# Nucleo_Connector.net
KiCad netlist of a schematic drawn in Altium Designer
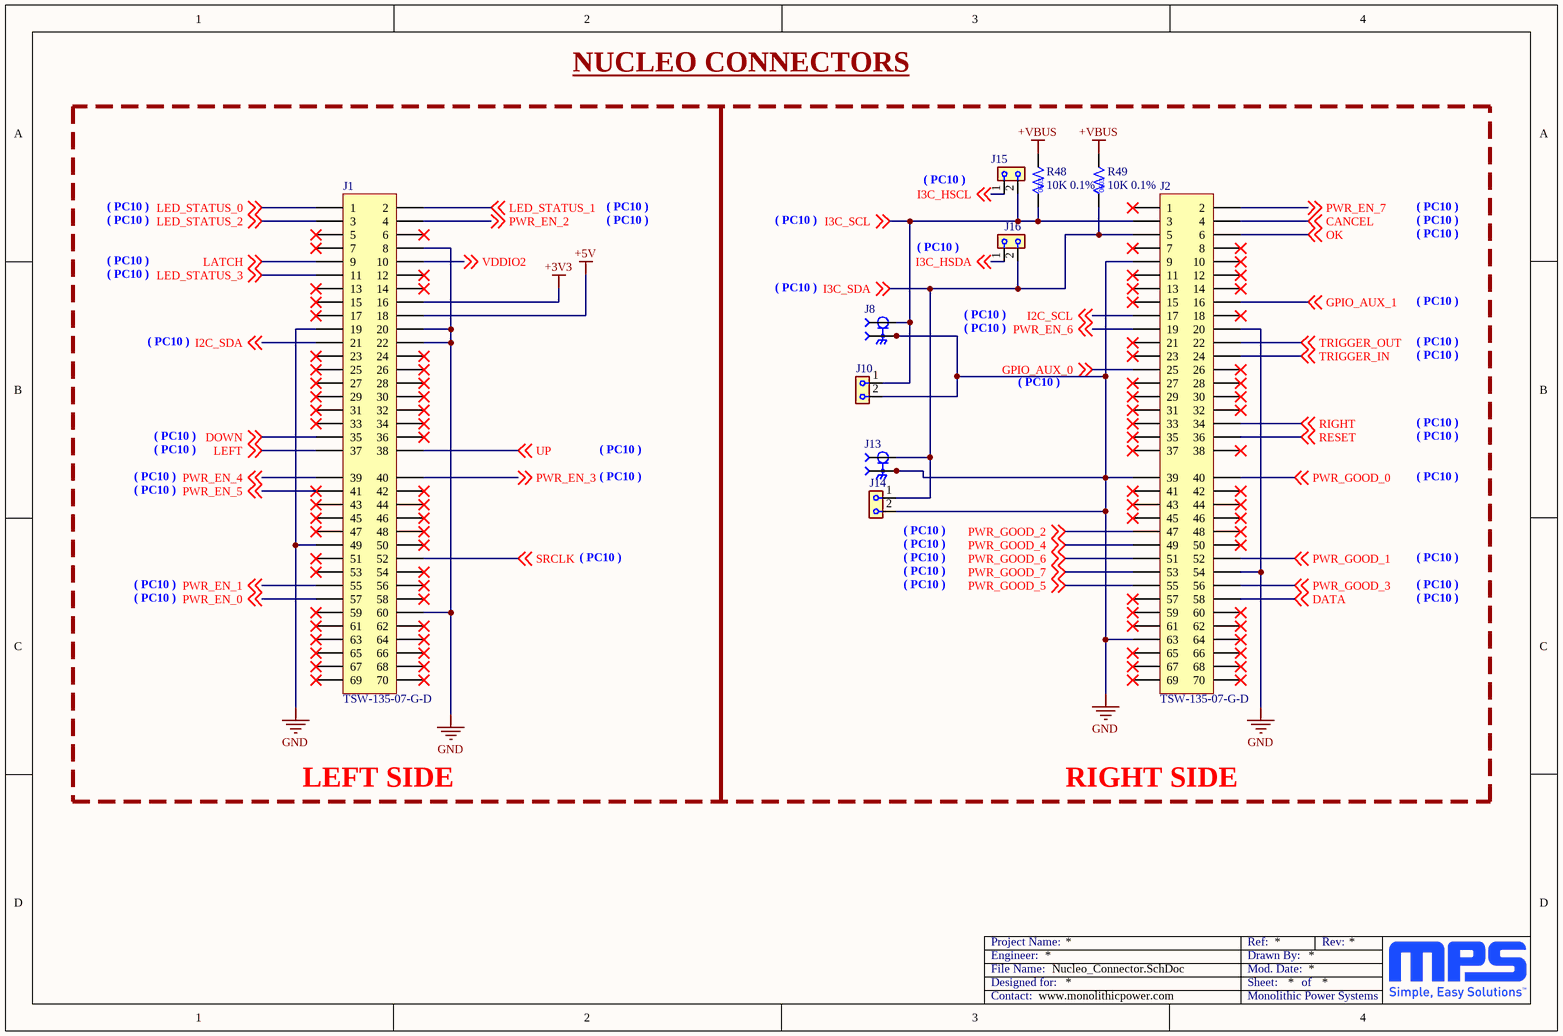
[diagram p0: Nucleo_Connector.SchDoc]

(export (version "E")
  (design (tool "Eeschema 10.0.6"))
  (components
    (comp (ref "J1")
      (value "TSW-135-07-G-D")
      (footprint "CON_SAMTEC_TSW-135-07-X-D")
      (description "Header, 35x2, 2,54mm, VR, TH, Height 5.84mm/2.54mm")
      (fields (field (name "MANUFACTURER") "Samtec"))
      (libsource (lib "DDR5_Nucleo_Shield_Symbols") (part "TSW-135-07-G-D"))
    )
    (comp (ref "J2")
      (value "TSW-135-07-G-D")
      (footprint "CON_SAMTEC_TSW-135-07-X-D")
      (description "Header, 35x2, 2,54mm, VR, TH, Height 5.84mm/2.54mm")
      (fields (field (name "MANUFACTURER") "Samtec"))
      (libsource (lib "DDR5_Nucleo_Shield_Symbols") (part "TSW-135-07-G-D"))
    )
    (comp (ref "J8")
      (value "MMCX-J-P-H-ST-TH1")
      (footprint "SAMTEC_MMCX-J-P-H-ST-TH1")
      (description "RF Connectors / Coaxial Connectors 50 OHM MMCX JACK OR PLUG")
      (fields (field (name "MANUFACTURER") "Samtec Inc."))
      (libsource (lib "DDR5_Nucleo_Shield_Symbols") (part "MMCX-J-P-H-ST-TH1"))
    )
    (comp (ref "J10")
      (value "TSW-102-07-F-S")
      (footprint "HEADER/VERT/1X2/M/P2.54")
      (description "Alojamientos de cables y cabecera 2.54MM CLASSIC PCB HDR STRIP")
      (fields (field (name "MANUFACTURER") "SAMTEC"))
      (libsource (lib "") (part "TSW-102-07-F-S_1"))
    )
    (comp (ref "J13")
      (value "MMCX-J-P-H-ST-TH1")
      (footprint "SAMTEC_MMCX-J-P-H-ST-TH1")
      (description "RF Connectors / Coaxial Connectors 50 OHM MMCX JACK OR PLUG")
      (fields (field (name "MANUFACTURER") "Samtec Inc."))
      (libsource (lib "DDR5_Nucleo_Shield_Symbols") (part "MMCX-J-P-H-ST-TH1"))
    )
    (comp (ref "J14")
      (value "TSW-102-07-F-S")
      (footprint "HEADER/VERT/1X2/M/P2.54")
      (description "Alojamientos de cables y cabecera 2.54MM CLASSIC PCB HDR STRIP")
      (fields (field (name "MANUFACTURER") "SAMTEC"))
      (libsource (lib "") (part "TSW-102-07-F-S_1"))
    )
    (comp (ref "J15")
      (value "TSW-102-07-F-S")
      (footprint "HEADER/VERT/1X2/M/P2.54")
      (description "Alojamientos de cables y cabecera 2.54MM CLASSIC PCB HDR STRIP")
      (fields (field (name "MANUFACTURER") "SAMTEC"))
      (libsource (lib "DDR5_Nucleo_Shield_Symbols") (part "TSW-102-07-F-S"))
    )
    (comp (ref "J16")
      (value "TSW-102-07-F-S")
      (footprint "HEADER/VERT/1X2/M/P2.54")
      (description "Alojamientos de cables y cabecera 2.54MM CLASSIC PCB HDR STRIP")
      (fields (field (name "MANUFACTURER") "SAMTEC"))
      (libsource (lib "DDR5_Nucleo_Shield_Symbols") (part "TSW-102-07-F-S"))
    )
    (comp (ref "R48")
      (value "10K 0.1%")
      (footprint "CC/NM 0603")
      (description "Thin Film Resistors - SMD 1/10watts 10K .1%")
      (fields
        (field (name "MANUFACTURER") "Bourns")
        (field (name "MANUFACTURER PART NUMBER") "CRT0603-BY-1002ELF")
      )
      (libsource (lib "DDR5_Nucleo_Shield_Symbols") (part "CRT0603-BY-1002ELF"))
    )
    (comp (ref "R49")
      (value "10K 0.1%")
      (footprint "CC/NM 0603")
      (description "Thin Film Resistors - SMD 1/10watts 10K .1%")
      (fields
        (field (name "MANUFACTURER") "Bourns")
        (field (name "MANUFACTURER PART NUMBER") "CRT0603-BY-1002ELF")
      )
      (libsource (lib "DDR5_Nucleo_Shield_Symbols") (part "CRT0603-BY-1002ELF"))
    )
  )
  (nets
    (net (code "1") (name "+3V3") (class "Default")
      (node (ref "J1") (pin "16") (pinfunction "16_16") (pintype "passive"))
    )
    (net (code "2") (name "+5V") (class "Default")
      (node (ref "J1") (pin "18") (pinfunction "18_18") (pintype "passive"))
    )
    (net (code "3") (name "+VBUS") (class "Default")
      (node (ref "R48") (pin "2") (pinfunction "2_2") (pintype "passive"))
      (node (ref "R49") (pin "2") (pinfunction "2_2") (pintype "passive"))
    )
    (net (code "4") (name "CANCEL") (class "Default")
      (node (ref "J2") (pin "4") (pinfunction "4_4") (pintype "passive"))
    )
    (net (code "5") (name "DATA") (class "Default")
      (node (ref "J2") (pin "58") (pinfunction "58_58") (pintype "passive"))
    )
    (net (code "6") (name "DOWN") (class "Default")
      (node (ref "J1") (pin "35") (pinfunction "35_35") (pintype "passive"))
    )
    (net (code "7") (name "GND") (class "Default")
      (node (ref "J1") (pin "19") (pinfunction "19_19") (pintype "passive"))
      (node (ref "J1") (pin "20") (pinfunction "20_20") (pintype "passive"))
      (node (ref "J1") (pin "22") (pinfunction "22_22") (pintype "passive"))
      (node (ref "J1") (pin "49") (pinfunction "49_49") (pintype "passive"))
      (node (ref "J1") (pin "60") (pinfunction "60_60") (pintype "passive"))
      (node (ref "J1") (pin "8") (pinfunction "8_8") (pintype "passive"))
      (node (ref "J10") (pin "2") (pinfunction "2_2") (pintype "passive"))
      (node (ref "J13") (pin "S1") (pinfunction "2_S1") (pintype "passive"))
      (node (ref "J13") (pin "S2") (pinfunction "2_S2") (pintype "passive"))
      (node (ref "J13") (pin "S3") (pinfunction "2_S3") (pintype "passive"))
      (node (ref "J13") (pin "S4") (pinfunction "2_S4") (pintype "passive"))
      (node (ref "J14") (pin "2") (pinfunction "2_2") (pintype "passive"))
      (node (ref "J2") (pin "20") (pinfunction "20_20") (pintype "passive"))
      (node (ref "J2") (pin "39") (pinfunction "39_39") (pintype "passive"))
      (node (ref "J2") (pin "54") (pinfunction "54_54") (pintype "passive"))
      (node (ref "J2") (pin "63") (pinfunction "63_63") (pintype "passive"))
      (node (ref "J2") (pin "9") (pinfunction "9_9") (pintype "passive"))
      (node (ref "J8") (pin "S1") (pinfunction "2_S1") (pintype "passive"))
      (node (ref "J8") (pin "S2") (pinfunction "2_S2") (pintype "passive"))
      (node (ref "J8") (pin "S3") (pinfunction "2_S3") (pintype "passive"))
      (node (ref "J8") (pin "S4") (pinfunction "2_S4") (pintype "passive"))
    )
    (net (code "8") (name "GPIO_AUX_0") (class "Default")
      (node (ref "J2") (pin "25") (pinfunction "25_25") (pintype "passive"))
    )
    (net (code "9") (name "GPIO_AUX_1") (class "Default")
      (node (ref "J2") (pin "16") (pinfunction "16_16") (pintype "passive"))
    )
    (net (code "10") (name "I2C_SCL") (class "Default")
      (node (ref "J2") (pin "17") (pinfunction "17_17") (pintype "passive"))
    )
    (net (code "11") (name "I2C_SDA") (class "Default")
      (node (ref "J1") (pin "21") (pinfunction "21_21") (pintype "passive"))
    )
    (net (code "12") (name "I3C_HSCL") (class "Default")
      (node (ref "J15") (pin "1") (pinfunction "1_1") (pintype "passive"))
    )
    (net (code "13") (name "I3C_HSDA") (class "Default")
      (node (ref "J16") (pin "1") (pinfunction "1_1") (pintype "passive"))
    )
    (net (code "14") (name "I3C_SCL") (class "Default")
      (node (ref "J10") (pin "1") (pinfunction "1_1") (pintype "passive"))
      (node (ref "J15") (pin "2") (pinfunction "2_2") (pintype "passive"))
      (node (ref "J2") (pin "3") (pinfunction "3_3") (pintype "passive"))
      (node (ref "J8") (pin "1") (pinfunction "1_1") (pintype "passive"))
      (node (ref "R48") (pin "1") (pinfunction "1_1") (pintype "passive"))
    )
    (net (code "15") (name "I3C_SDA") (class "Default")
      (node (ref "J13") (pin "1") (pinfunction "1_1") (pintype "passive"))
      (node (ref "J14") (pin "1") (pinfunction "1_1") (pintype "passive"))
      (node (ref "J16") (pin "2") (pinfunction "2_2") (pintype "passive"))
      (node (ref "J2") (pin "5") (pinfunction "5_5") (pintype "passive"))
      (node (ref "R49") (pin "1") (pinfunction "1_1") (pintype "passive"))
    )
    (net (code "16") (name "LATCH") (class "Default")
      (node (ref "J1") (pin "9") (pinfunction "9_9") (pintype "passive"))
    )
    (net (code "17") (name "LED_STATUS_0") (class "Default")
      (node (ref "J1") (pin "1") (pinfunction "1_1") (pintype "passive"))
    )
    (net (code "18") (name "LED_STATUS_1") (class "Default")
      (node (ref "J1") (pin "2") (pinfunction "2_2") (pintype "passive"))
    )
    (net (code "19") (name "LED_STATUS_2") (class "Default")
      (node (ref "J1") (pin "3") (pinfunction "3_3") (pintype "passive"))
    )
    (net (code "20") (name "LED_STATUS_3") (class "Default")
      (node (ref "J1") (pin "11") (pinfunction "11_11") (pintype "passive"))
    )
    (net (code "21") (name "LEFT") (class "Default")
      (node (ref "J1") (pin "37") (pinfunction "37_37") (pintype "passive"))
    )
    (net (code "22") (name "OK") (class "Default")
      (node (ref "J2") (pin "6") (pinfunction "6_6") (pintype "passive"))
    )
    (net (code "23") (name "PWR_EN_0") (class "Default")
      (node (ref "J1") (pin "57") (pinfunction "57_57") (pintype "passive"))
    )
    (net (code "24") (name "PWR_EN_1") (class "Default")
      (node (ref "J1") (pin "55") (pinfunction "55_55") (pintype "passive"))
    )
    (net (code "25") (name "PWR_EN_2") (class "Default")
      (node (ref "J1") (pin "4") (pinfunction "4_4") (pintype "passive"))
    )
    (net (code "26") (name "PWR_EN_3") (class "Default")
      (node (ref "J1") (pin "40") (pinfunction "40_40") (pintype "passive"))
    )
    (net (code "27") (name "PWR_EN_4") (class "Default")
      (node (ref "J1") (pin "39") (pinfunction "39_39") (pintype "passive"))
    )
    (net (code "28") (name "PWR_EN_5") (class "Default")
      (node (ref "J1") (pin "41") (pinfunction "41_41") (pintype "passive"))
    )
    (net (code "29") (name "PWR_EN_6") (class "Default")
      (node (ref "J2") (pin "19") (pinfunction "19_19") (pintype "passive"))
    )
    (net (code "30") (name "PWR_EN_7") (class "Default")
      (node (ref "J2") (pin "2") (pinfunction "2_2") (pintype "passive"))
    )
    (net (code "31") (name "PWR_GOOD_0") (class "Default")
      (node (ref "J2") (pin "40") (pinfunction "40_40") (pintype "passive"))
    )
    (net (code "32") (name "PWR_GOOD_1") (class "Default")
      (node (ref "J2") (pin "52") (pinfunction "52_52") (pintype "passive"))
    )
    (net (code "33") (name "PWR_GOOD_2") (class "Default")
      (node (ref "J2") (pin "47") (pinfunction "47_47") (pintype "passive"))
    )
    (net (code "34") (name "PWR_GOOD_3") (class "Default")
      (node (ref "J2") (pin "56") (pinfunction "56_56") (pintype "passive"))
    )
    (net (code "35") (name "PWR_GOOD_4") (class "Default")
      (node (ref "J2") (pin "49") (pinfunction "49_49") (pintype "passive"))
    )
    (net (code "36") (name "PWR_GOOD_5") (class "Default")
      (node (ref "J2") (pin "55") (pinfunction "55_55") (pintype "passive"))
    )
    (net (code "37") (name "PWR_GOOD_6") (class "Default")
      (node (ref "J2") (pin "51") (pinfunction "51_51") (pintype "passive"))
    )
    (net (code "38") (name "PWR_GOOD_7") (class "Default")
      (node (ref "J2") (pin "53") (pinfunction "53_53") (pintype "passive"))
    )
    (net (code "39") (name "RESET") (class "Default")
      (node (ref "J2") (pin "36") (pinfunction "36_36") (pintype "passive"))
    )
    (net (code "40") (name "RIGHT") (class "Default")
      (node (ref "J2") (pin "34") (pinfunction "34_34") (pintype "passive"))
    )
    (net (code "41") (name "SRCLK") (class "Default")
      (node (ref "J1") (pin "52") (pinfunction "52_52") (pintype "passive"))
    )
    (net (code "42") (name "TRIGGER_IN") (class "Default")
      (node (ref "J2") (pin "24") (pinfunction "24_24") (pintype "passive"))
    )
    (net (code "43") (name "TRIGGER_OUT") (class "Default")
      (node (ref "J2") (pin "22") (pinfunction "22_22") (pintype "passive"))
    )
    (net (code "44") (name "UP") (class "Default")
      (node (ref "J1") (pin "38") (pinfunction "38_38") (pintype "passive"))
    )
    (net (code "45") (name "VDDIO2") (class "Default")
      (node (ref "J1") (pin "10") (pinfunction "10_10") (pintype "passive"))
    )
    (net (code "46") (name "unconnected-(J1-Pad5)") (class "Default")
      (node (ref "J1") (pin "5") (pinfunction "5_5") (pintype "passive+no_connect"))
    )
    (net (code "47") (name "unconnected-(J1-Pad6)") (class "Default")
      (node (ref "J1") (pin "6") (pinfunction "6_6") (pintype "passive+no_connect"))
    )
    (net (code "48") (name "unconnected-(J1-Pad7)") (class "Default")
      (node (ref "J1") (pin "7") (pinfunction "7_7") (pintype "passive+no_connect"))
    )
    (net (code "49") (name "unconnected-(J1-Pad12)") (class "Default")
      (node (ref "J1") (pin "12") (pinfunction "12_12") (pintype "passive+no_connect"))
    )
    (net (code "50") (name "unconnected-(J1-Pad13)") (class "Default")
      (node (ref "J1") (pin "13") (pinfunction "13_13") (pintype "passive+no_connect"))
    )
    (net (code "51") (name "unconnected-(J1-Pad14)") (class "Default")
      (node (ref "J1") (pin "14") (pinfunction "14_14") (pintype "passive+no_connect"))
    )
    (net (code "52") (name "unconnected-(J1-Pad15)") (class "Default")
      (node (ref "J1") (pin "15") (pinfunction "15_15") (pintype "passive+no_connect"))
    )
    (net (code "53") (name "unconnected-(J1-Pad17)") (class "Default")
      (node (ref "J1") (pin "17") (pinfunction "17_17") (pintype "passive+no_connect"))
    )
    (net (code "54") (name "unconnected-(J1-Pad23)") (class "Default")
      (node (ref "J1") (pin "23") (pinfunction "23_23") (pintype "passive+no_connect"))
    )
    (net (code "55") (name "unconnected-(J1-Pad24)") (class "Default")
      (node (ref "J1") (pin "24") (pinfunction "24_24") (pintype "passive+no_connect"))
    )
    (net (code "56") (name "unconnected-(J1-Pad25)") (class "Default")
      (node (ref "J1") (pin "25") (pinfunction "25_25") (pintype "passive+no_connect"))
    )
    (net (code "57") (name "unconnected-(J1-Pad26)") (class "Default")
      (node (ref "J1") (pin "26") (pinfunction "26_26") (pintype "passive+no_connect"))
    )
    (net (code "58") (name "unconnected-(J1-Pad27)") (class "Default")
      (node (ref "J1") (pin "27") (pinfunction "27_27") (pintype "passive+no_connect"))
    )
    (net (code "59") (name "unconnected-(J1-Pad28)") (class "Default")
      (node (ref "J1") (pin "28") (pinfunction "28_28") (pintype "passive+no_connect"))
    )
    (net (code "60") (name "unconnected-(J1-Pad29)") (class "Default")
      (node (ref "J1") (pin "29") (pinfunction "29_29") (pintype "passive+no_connect"))
    )
    (net (code "61") (name "unconnected-(J1-Pad30)") (class "Default")
      (node (ref "J1") (pin "30") (pinfunction "30_30") (pintype "passive+no_connect"))
    )
    (net (code "62") (name "unconnected-(J1-Pad31)") (class "Default")
      (node (ref "J1") (pin "31") (pinfunction "31_31") (pintype "passive+no_connect"))
    )
    (net (code "63") (name "unconnected-(J1-Pad32)") (class "Default")
      (node (ref "J1") (pin "32") (pinfunction "32_32") (pintype "passive+no_connect"))
    )
    (net (code "64") (name "unconnected-(J1-Pad33)") (class "Default")
      (node (ref "J1") (pin "33") (pinfunction "33_33") (pintype "passive+no_connect"))
    )
    (net (code "65") (name "unconnected-(J1-Pad34)") (class "Default")
      (node (ref "J1") (pin "34") (pinfunction "34_34") (pintype "passive+no_connect"))
    )
    (net (code "66") (name "unconnected-(J1-Pad36)") (class "Default")
      (node (ref "J1") (pin "36") (pinfunction "36_36") (pintype "passive+no_connect"))
    )
    (net (code "67") (name "unconnected-(J1-Pad42)") (class "Default")
      (node (ref "J1") (pin "42") (pinfunction "42_42") (pintype "passive+no_connect"))
    )
    (net (code "68") (name "unconnected-(J1-Pad43)") (class "Default")
      (node (ref "J1") (pin "43") (pinfunction "43_43") (pintype "passive+no_connect"))
    )
    (net (code "69") (name "unconnected-(J1-Pad44)") (class "Default")
      (node (ref "J1") (pin "44") (pinfunction "44_44") (pintype "passive+no_connect"))
    )
    (net (code "70") (name "unconnected-(J1-Pad45)") (class "Default")
      (node (ref "J1") (pin "45") (pinfunction "45_45") (pintype "passive+no_connect"))
    )
    (net (code "71") (name "unconnected-(J1-Pad46)") (class "Default")
      (node (ref "J1") (pin "46") (pinfunction "46_46") (pintype "passive+no_connect"))
    )
    (net (code "72") (name "unconnected-(J1-Pad47)") (class "Default")
      (node (ref "J1") (pin "47") (pinfunction "47_47") (pintype "passive+no_connect"))
    )
    (net (code "73") (name "unconnected-(J1-Pad48)") (class "Default")
      (node (ref "J1") (pin "48") (pinfunction "48_48") (pintype "passive+no_connect"))
    )
    (net (code "74") (name "unconnected-(J1-Pad50)") (class "Default")
      (node (ref "J1") (pin "50") (pinfunction "50_50") (pintype "passive+no_connect"))
    )
    (net (code "75") (name "unconnected-(J1-Pad51)") (class "Default")
      (node (ref "J1") (pin "51") (pinfunction "51_51") (pintype "passive+no_connect"))
    )
    (net (code "76") (name "unconnected-(J1-Pad53)") (class "Default")
      (node (ref "J1") (pin "53") (pinfunction "53_53") (pintype "passive+no_connect"))
    )
    (net (code "77") (name "unconnected-(J1-Pad54)") (class "Default")
      (node (ref "J1") (pin "54") (pinfunction "54_54") (pintype "passive+no_connect"))
    )
    (net (code "78") (name "unconnected-(J1-Pad56)") (class "Default")
      (node (ref "J1") (pin "56") (pinfunction "56_56") (pintype "passive+no_connect"))
    )
    (net (code "79") (name "unconnected-(J1-Pad58)") (class "Default")
      (node (ref "J1") (pin "58") (pinfunction "58_58") (pintype "passive+no_connect"))
    )
    (net (code "80") (name "unconnected-(J1-Pad59)") (class "Default")
      (node (ref "J1") (pin "59") (pinfunction "59_59") (pintype "passive+no_connect"))
    )
    (net (code "81") (name "unconnected-(J1-Pad61)") (class "Default")
      (node (ref "J1") (pin "61") (pinfunction "61_61") (pintype "passive+no_connect"))
    )
    (net (code "82") (name "unconnected-(J1-Pad62)") (class "Default")
      (node (ref "J1") (pin "62") (pinfunction "62_62") (pintype "passive+no_connect"))
    )
    (net (code "83") (name "unconnected-(J1-Pad63)") (class "Default")
      (node (ref "J1") (pin "63") (pinfunction "63_63") (pintype "passive+no_connect"))
    )
    (net (code "84") (name "unconnected-(J1-Pad64)") (class "Default")
      (node (ref "J1") (pin "64") (pinfunction "64_64") (pintype "passive+no_connect"))
    )
    (net (code "85") (name "unconnected-(J1-Pad65)") (class "Default")
      (node (ref "J1") (pin "65") (pinfunction "65_65") (pintype "passive+no_connect"))
    )
    (net (code "86") (name "unconnected-(J1-Pad66)") (class "Default")
      (node (ref "J1") (pin "66") (pinfunction "66_66") (pintype "passive+no_connect"))
    )
    (net (code "87") (name "unconnected-(J1-Pad67)") (class "Default")
      (node (ref "J1") (pin "67") (pinfunction "67_67") (pintype "passive+no_connect"))
    )
    (net (code "88") (name "unconnected-(J1-Pad68)") (class "Default")
      (node (ref "J1") (pin "68") (pinfunction "68_68") (pintype "passive+no_connect"))
    )
    (net (code "89") (name "unconnected-(J1-Pad69)") (class "Default")
      (node (ref "J1") (pin "69") (pinfunction "69_69") (pintype "passive+no_connect"))
    )
    (net (code "90") (name "unconnected-(J1-Pad70)") (class "Default")
      (node (ref "J1") (pin "70") (pinfunction "70_70") (pintype "passive+no_connect"))
    )
    (net (code "91") (name "unconnected-(J2-Pad1)") (class "Default")
      (node (ref "J2") (pin "1") (pinfunction "1_1") (pintype "passive+no_connect"))
    )
    (net (code "92") (name "unconnected-(J2-Pad7)") (class "Default")
      (node (ref "J2") (pin "7") (pinfunction "7_7") (pintype "passive+no_connect"))
    )
    (net (code "93") (name "unconnected-(J2-Pad8)") (class "Default")
      (node (ref "J2") (pin "8") (pinfunction "8_8") (pintype "passive+no_connect"))
    )
    (net (code "94") (name "unconnected-(J2-Pad10)") (class "Default")
      (node (ref "J2") (pin "10") (pinfunction "10_10") (pintype "passive+no_connect"))
    )
    (net (code "95") (name "unconnected-(J2-Pad11)") (class "Default")
      (node (ref "J2") (pin "11") (pinfunction "11_11") (pintype "passive+no_connect"))
    )
    (net (code "96") (name "unconnected-(J2-Pad12)") (class "Default")
      (node (ref "J2") (pin "12") (pinfunction "12_12") (pintype "passive+no_connect"))
    )
    (net (code "97") (name "unconnected-(J2-Pad13)") (class "Default")
      (node (ref "J2") (pin "13") (pinfunction "13_13") (pintype "passive+no_connect"))
    )
    (net (code "98") (name "unconnected-(J2-Pad14)") (class "Default")
      (node (ref "J2") (pin "14") (pinfunction "14_14") (pintype "passive+no_connect"))
    )
    (net (code "99") (name "unconnected-(J2-Pad15)") (class "Default")
      (node (ref "J2") (pin "15") (pinfunction "15_15") (pintype "passive+no_connect"))
    )
    (net (code "100") (name "unconnected-(J2-Pad18)") (class "Default")
      (node (ref "J2") (pin "18") (pinfunction "18_18") (pintype "passive+no_connect"))
    )
    (net (code "101") (name "unconnected-(J2-Pad21)") (class "Default")
      (node (ref "J2") (pin "21") (pinfunction "21_21") (pintype "passive+no_connect"))
    )
    (net (code "102") (name "unconnected-(J2-Pad23)") (class "Default")
      (node (ref "J2") (pin "23") (pinfunction "23_23") (pintype "passive+no_connect"))
    )
    (net (code "103") (name "unconnected-(J2-Pad26)") (class "Default")
      (node (ref "J2") (pin "26") (pinfunction "26_26") (pintype "passive+no_connect"))
    )
    (net (code "104") (name "unconnected-(J2-Pad27)") (class "Default")
      (node (ref "J2") (pin "27") (pinfunction "27_27") (pintype "passive+no_connect"))
    )
    (net (code "105") (name "unconnected-(J2-Pad28)") (class "Default")
      (node (ref "J2") (pin "28") (pinfunction "28_28") (pintype "passive+no_connect"))
    )
    (net (code "106") (name "unconnected-(J2-Pad29)") (class "Default")
      (node (ref "J2") (pin "29") (pinfunction "29_29") (pintype "passive+no_connect"))
    )
    (net (code "107") (name "unconnected-(J2-Pad30)") (class "Default")
      (node (ref "J2") (pin "30") (pinfunction "30_30") (pintype "passive+no_connect"))
    )
    (net (code "108") (name "unconnected-(J2-Pad31)") (class "Default")
      (node (ref "J2") (pin "31") (pinfunction "31_31") (pintype "passive+no_connect"))
    )
    (net (code "109") (name "unconnected-(J2-Pad32)") (class "Default")
      (node (ref "J2") (pin "32") (pinfunction "32_32") (pintype "passive+no_connect"))
    )
    (net (code "110") (name "unconnected-(J2-Pad33)") (class "Default")
      (node (ref "J2") (pin "33") (pinfunction "33_33") (pintype "passive+no_connect"))
    )
    (net (code "111") (name "unconnected-(J2-Pad35)") (class "Default")
      (node (ref "J2") (pin "35") (pinfunction "35_35") (pintype "passive+no_connect"))
    )
    (net (code "112") (name "unconnected-(J2-Pad37)") (class "Default")
      (node (ref "J2") (pin "37") (pinfunction "37_37") (pintype "passive+no_connect"))
    )
    (net (code "113") (name "unconnected-(J2-Pad38)") (class "Default")
      (node (ref "J2") (pin "38") (pinfunction "38_38") (pintype "passive+no_connect"))
    )
    (net (code "114") (name "unconnected-(J2-Pad41)") (class "Default")
      (node (ref "J2") (pin "41") (pinfunction "41_41") (pintype "passive+no_connect"))
    )
    (net (code "115") (name "unconnected-(J2-Pad42)") (class "Default")
      (node (ref "J2") (pin "42") (pinfunction "42_42") (pintype "passive+no_connect"))
    )
    (net (code "116") (name "unconnected-(J2-Pad43)") (class "Default")
      (node (ref "J2") (pin "43") (pinfunction "43_43") (pintype "passive+no_connect"))
    )
    (net (code "117") (name "unconnected-(J2-Pad44)") (class "Default")
      (node (ref "J2") (pin "44") (pinfunction "44_44") (pintype "passive+no_connect"))
    )
    (net (code "118") (name "unconnected-(J2-Pad45)") (class "Default")
      (node (ref "J2") (pin "45") (pinfunction "45_45") (pintype "passive+no_connect"))
    )
    (net (code "119") (name "unconnected-(J2-Pad46)") (class "Default")
      (node (ref "J2") (pin "46") (pinfunction "46_46") (pintype "passive+no_connect"))
    )
    (net (code "120") (name "unconnected-(J2-Pad48)") (class "Default")
      (node (ref "J2") (pin "48") (pinfunction "48_48") (pintype "passive+no_connect"))
    )
    (net (code "121") (name "unconnected-(J2-Pad50)") (class "Default")
      (node (ref "J2") (pin "50") (pinfunction "50_50") (pintype "passive+no_connect"))
    )
    (net (code "122") (name "unconnected-(J2-Pad57)") (class "Default")
      (node (ref "J2") (pin "57") (pinfunction "57_57") (pintype "passive+no_connect"))
    )
    (net (code "123") (name "unconnected-(J2-Pad59)") (class "Default")
      (node (ref "J2") (pin "59") (pinfunction "59_59") (pintype "passive+no_connect"))
    )
    (net (code "124") (name "unconnected-(J2-Pad60)") (class "Default")
      (node (ref "J2") (pin "60") (pinfunction "60_60") (pintype "passive+no_connect"))
    )
    (net (code "125") (name "unconnected-(J2-Pad61)") (class "Default")
      (node (ref "J2") (pin "61") (pinfunction "61_61") (pintype "passive+no_connect"))
    )
    (net (code "126") (name "unconnected-(J2-Pad62)") (class "Default")
      (node (ref "J2") (pin "62") (pinfunction "62_62") (pintype "passive+no_connect"))
    )
    (net (code "127") (name "unconnected-(J2-Pad64)") (class "Default")
      (node (ref "J2") (pin "64") (pinfunction "64_64") (pintype "passive+no_connect"))
    )
    (net (code "128") (name "unconnected-(J2-Pad65)") (class "Default")
      (node (ref "J2") (pin "65") (pinfunction "65_65") (pintype "passive+no_connect"))
    )
    (net (code "129") (name "unconnected-(J2-Pad66)") (class "Default")
      (node (ref "J2") (pin "66") (pinfunction "66_66") (pintype "passive+no_connect"))
    )
    (net (code "130") (name "unconnected-(J2-Pad67)") (class "Default")
      (node (ref "J2") (pin "67") (pinfunction "67_67") (pintype "passive+no_connect"))
    )
    (net (code "131") (name "unconnected-(J2-Pad68)") (class "Default")
      (node (ref "J2") (pin "68") (pinfunction "68_68") (pintype "passive+no_connect"))
    )
    (net (code "132") (name "unconnected-(J2-Pad69)") (class "Default")
      (node (ref "J2") (pin "69") (pinfunction "69_69") (pintype "passive+no_connect"))
    )
    (net (code "133") (name "unconnected-(J2-Pad70)") (class "Default")
      (node (ref "J2") (pin "70") (pinfunction "70_70") (pintype "passive+no_connect"))
    )
  )
)
